# Bank35.net
KiCad netlist of a schematic drawn in Altium Designer
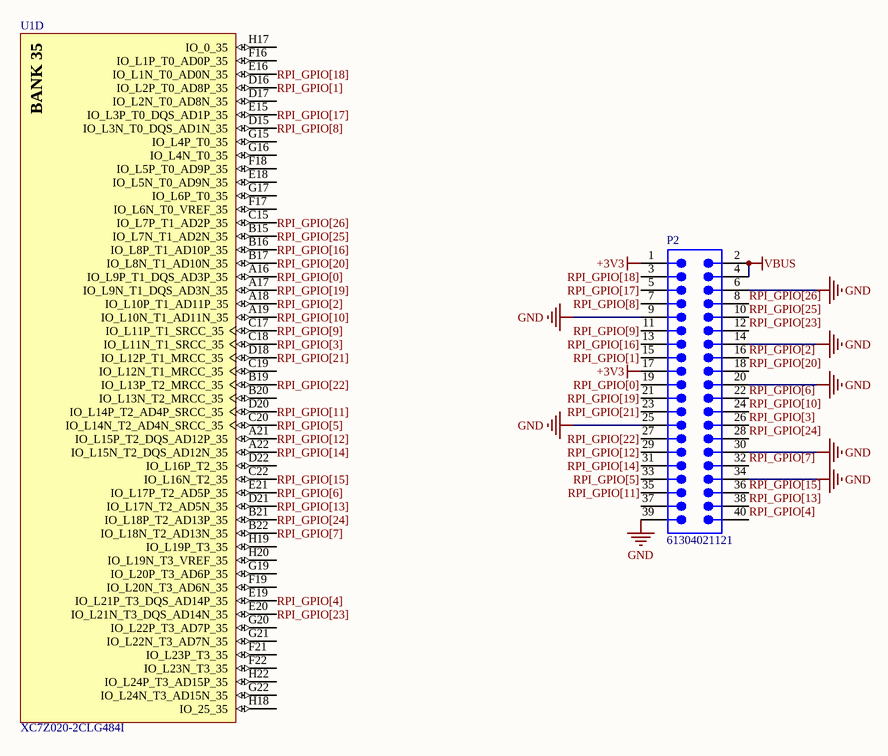
[diagram p0: Bank35.SchDoc]

(export (version "E")
  (design (tool "Eeschema 10.0.6"))
  (components
    (comp (ref "P2")
      (value "61304021121")
      (footprint "61304021121")
      (libsource (lib "Altium Content Vault") (part "Header_Male_2R_40P"))
    )
    (comp (ref "U1")
      (value "XC7Z020-2CLG484I")
      (footprint "CLG484")
      (fields (field (name "GENERIC PART NUMBER") "XC7Z020"))
      (libsource (lib "Altium Content Vault") (part "XNLX-XC7Z020-CLG484"))
    )
  )
  (nets
    (net (code "1") (name "+3V3") (class "Default")
      (node (ref "P2") (pin "1") (pinfunction "1_1") (pintype "passive"))
      (node (ref "P2") (pin "17") (pinfunction "17_17") (pintype "passive"))
    )
    (net (code "2") (name "/RPI_GPIO[0]") (class "Default")
      (node (ref "P2") (pin "19") (pinfunction "19_19") (pintype "passive"))
      (node (ref "U1") (pin "A16") (pinfunction "IO_L9P_T1_DQS_AD3P_35_A16") (pintype "bidirectional"))
    )
    (net (code "3") (name "/RPI_GPIO[1]") (class "Default")
      (node (ref "P2") (pin "15") (pinfunction "15_15") (pintype "passive"))
      (node (ref "U1") (pin "D16") (pinfunction "IO_L2P_T0_AD8P_35_D16") (pintype "bidirectional"))
    )
    (net (code "4") (name "/RPI_GPIO[2]") (class "Default")
      (node (ref "P2") (pin "16") (pinfunction "16_16") (pintype "passive"))
      (node (ref "U1") (pin "A18") (pinfunction "IO_L10P_T1_AD11P_35_A18") (pintype "bidirectional"))
    )
    (net (code "5") (name "/RPI_GPIO[3]") (class "Default")
      (node (ref "P2") (pin "26") (pinfunction "26_26") (pintype "passive"))
      (node (ref "U1") (pin "C18") (pinfunction "IO_L11N_T1_SRCC_35_C18") (pintype "bidirectional"))
    )
    (net (code "6") (name "/RPI_GPIO[4]") (class "Default")
      (node (ref "P2") (pin "40") (pinfunction "40_40") (pintype "passive"))
      (node (ref "U1") (pin "E19") (pinfunction "IO_L21P_T3_DQS_AD14P_35_E19") (pintype "bidirectional"))
    )
    (net (code "7") (name "/RPI_GPIO[5]") (class "Default")
      (node (ref "P2") (pin "33") (pinfunction "33_33") (pintype "passive"))
      (node (ref "U1") (pin "C20") (pinfunction "IO_L14N_T2_AD4N_SRCC_35_C20") (pintype "bidirectional"))
    )
    (net (code "8") (name "/RPI_GPIO[6]") (class "Default")
      (node (ref "P2") (pin "22") (pinfunction "22_22") (pintype "passive"))
      (node (ref "U1") (pin "E21") (pinfunction "IO_L17P_T2_AD5P_35_E21") (pintype "bidirectional"))
    )
    (net (code "9") (name "/RPI_GPIO[7]") (class "Default")
      (node (ref "P2") (pin "32") (pinfunction "32_32") (pintype "passive"))
      (node (ref "U1") (pin "B22") (pinfunction "IO_L18N_T2_AD13N_35_B22") (pintype "bidirectional"))
    )
    (net (code "10") (name "/RPI_GPIO[8]") (class "Default")
      (node (ref "P2") (pin "7") (pinfunction "7_7") (pintype "passive"))
      (node (ref "U1") (pin "D15") (pinfunction "IO_L3N_T0_DQS_AD1N_35_D15") (pintype "bidirectional"))
    )
    (net (code "11") (name "/RPI_GPIO[9]") (class "Default")
      (node (ref "P2") (pin "11") (pinfunction "11_11") (pintype "passive"))
      (node (ref "U1") (pin "C17") (pinfunction "IO_L11P_T1_SRCC_35_C17") (pintype "bidirectional"))
    )
    (net (code "12") (name "/RPI_GPIO[10]") (class "Default")
      (node (ref "P2") (pin "24") (pinfunction "24_24") (pintype "passive"))
      (node (ref "U1") (pin "A19") (pinfunction "IO_L10N_T1_AD11N_35_A19") (pintype "bidirectional"))
    )
    (net (code "13") (name "/RPI_GPIO[11]") (class "Default")
      (node (ref "P2") (pin "35") (pinfunction "35_35") (pintype "passive"))
      (node (ref "U1") (pin "D20") (pinfunction "IO_L14P_T2_AD4P_SRCC_35_D20") (pintype "bidirectional"))
    )
    (net (code "14") (name "/RPI_GPIO[12]") (class "Default")
      (node (ref "P2") (pin "29") (pinfunction "29_29") (pintype "passive"))
      (node (ref "U1") (pin "A21") (pinfunction "IO_L15P_T2_DQS_AD12P_35_A21") (pintype "bidirectional"))
    )
    (net (code "15") (name "/RPI_GPIO[13]") (class "Default")
      (node (ref "P2") (pin "38") (pinfunction "38_38") (pintype "passive"))
      (node (ref "U1") (pin "D21") (pinfunction "IO_L17N_T2_AD5N_35_D21") (pintype "bidirectional"))
    )
    (net (code "16") (name "/RPI_GPIO[14]") (class "Default")
      (node (ref "P2") (pin "31") (pinfunction "31_31") (pintype "passive"))
      (node (ref "U1") (pin "A22") (pinfunction "IO_L15N_T2_DQS_AD12N_35_A22") (pintype "bidirectional"))
    )
    (net (code "17") (name "/RPI_GPIO[15]") (class "Default")
      (node (ref "P2") (pin "36") (pinfunction "36_36") (pintype "passive"))
      (node (ref "U1") (pin "C22") (pinfunction "IO_L16N_T2_35_C22") (pintype "bidirectional"))
    )
    (net (code "18") (name "/RPI_GPIO[16]") (class "Default")
      (node (ref "P2") (pin "13") (pinfunction "13_13") (pintype "passive"))
      (node (ref "U1") (pin "B16") (pinfunction "IO_L8P_T1_AD10P_35_B16") (pintype "bidirectional"))
    )
    (net (code "19") (name "/RPI_GPIO[17]") (class "Default")
      (node (ref "P2") (pin "5") (pinfunction "5_5") (pintype "passive"))
      (node (ref "U1") (pin "E15") (pinfunction "IO_L3P_T0_DQS_AD1P_35_E15") (pintype "bidirectional"))
    )
    (net (code "20") (name "/RPI_GPIO[18]") (class "Default")
      (node (ref "P2") (pin "3") (pinfunction "3_3") (pintype "passive"))
      (node (ref "U1") (pin "E16") (pinfunction "IO_L1N_T0_AD0N_35_E16") (pintype "bidirectional"))
    )
    (net (code "21") (name "/RPI_GPIO[19]") (class "Default")
      (node (ref "P2") (pin "21") (pinfunction "21_21") (pintype "passive"))
      (node (ref "U1") (pin "A17") (pinfunction "IO_L9N_T1_DQS_AD3N_35_A17") (pintype "bidirectional"))
    )
    (net (code "22") (name "/RPI_GPIO[20]") (class "Default")
      (node (ref "P2") (pin "18") (pinfunction "18_18") (pintype "passive"))
      (node (ref "U1") (pin "B17") (pinfunction "IO_L8N_T1_AD10N_35_B17") (pintype "bidirectional"))
    )
    (net (code "23") (name "/RPI_GPIO[21]") (class "Default")
      (node (ref "P2") (pin "23") (pinfunction "23_23") (pintype "passive"))
      (node (ref "U1") (pin "D18") (pinfunction "IO_L12P_T1_MRCC_35_D18") (pintype "bidirectional"))
    )
    (net (code "24") (name "/RPI_GPIO[22]") (class "Default")
      (node (ref "P2") (pin "27") (pinfunction "27_27") (pintype "passive"))
      (node (ref "U1") (pin "B19") (pinfunction "IO_L13P_T2_MRCC_35_B19") (pintype "bidirectional"))
    )
    (net (code "25") (name "/RPI_GPIO[23]") (class "Default")
      (node (ref "P2") (pin "12") (pinfunction "12_12") (pintype "passive"))
      (node (ref "U1") (pin "E20") (pinfunction "IO_L21N_T3_DQS_AD14N_35_E20") (pintype "bidirectional"))
    )
    (net (code "26") (name "/RPI_GPIO[24]") (class "Default")
      (node (ref "P2") (pin "28") (pinfunction "28_28") (pintype "passive"))
      (node (ref "U1") (pin "B21") (pinfunction "IO_L18P_T2_AD13P_35_B21") (pintype "bidirectional"))
    )
    (net (code "27") (name "/RPI_GPIO[25]") (class "Default")
      (node (ref "P2") (pin "10") (pinfunction "10_10") (pintype "passive"))
      (node (ref "U1") (pin "B15") (pinfunction "IO_L7N_T1_AD2N_35_B15") (pintype "bidirectional"))
    )
    (net (code "28") (name "/RPI_GPIO[26]") (class "Default")
      (node (ref "P2") (pin "8") (pinfunction "8_8") (pintype "passive"))
      (node (ref "U1") (pin "C15") (pinfunction "IO_L7P_T1_AD2P_35_C15") (pintype "bidirectional"))
    )
    (net (code "29") (name "GND") (class "Default")
      (node (ref "P2") (pin "14") (pinfunction "14_14") (pintype "passive"))
      (node (ref "P2") (pin "20") (pinfunction "20_20") (pintype "passive"))
      (node (ref "P2") (pin "25") (pinfunction "25_25") (pintype "passive"))
      (node (ref "P2") (pin "30") (pinfunction "30_30") (pintype "passive"))
      (node (ref "P2") (pin "34") (pinfunction "34_34") (pintype "passive"))
      (node (ref "P2") (pin "39") (pinfunction "39_39") (pintype "passive"))
      (node (ref "P2") (pin "6") (pinfunction "6_6") (pintype "passive"))
      (node (ref "P2") (pin "9") (pinfunction "9_9") (pintype "passive"))
    )
    (net (code "30") (name "VBUS") (class "Default")
      (node (ref "P2") (pin "2") (pinfunction "2_2") (pintype "passive"))
      (node (ref "P2") (pin "4") (pinfunction "4_4") (pintype "passive"))
    )
    (net (code "31") (name "unconnected-(P2-Pad37)") (class "Default")
      (node (ref "P2") (pin "37") (pinfunction "37_37") (pintype "passive"))
    )
    (net (code "32") (name "unconnected-(U1D-IO_0_35-PadH17)") (class "Default")
      (node (ref "U1") (pin "H17") (pinfunction "IO_0_35_H17") (pintype "bidirectional"))
    )
    (net (code "33") (name "unconnected-(U1D-IO_25_35-PadH18)") (class "Default")
      (node (ref "U1") (pin "H18") (pinfunction "IO_25_35_H18") (pintype "bidirectional"))
    )
    (net (code "34") (name "unconnected-(U1D-IO_L1P_T0_AD0P_35-PadF16)") (class "Default")
      (node (ref "U1") (pin "F16") (pinfunction "IO_L1P_T0_AD0P_35_F16") (pintype "bidirectional"))
    )
    (net (code "35") (name "unconnected-(U1D-IO_L2N_T0_AD8N_35-PadD17)") (class "Default")
      (node (ref "U1") (pin "D17") (pinfunction "IO_L2N_T0_AD8N_35_D17") (pintype "bidirectional"))
    )
    (net (code "36") (name "unconnected-(U1D-IO_L4N_T0_35-PadG16)") (class "Default")
      (node (ref "U1") (pin "G16") (pinfunction "IO_L4N_T0_35_G16") (pintype "bidirectional"))
    )
    (net (code "37") (name "unconnected-(U1D-IO_L4P_T0_35-PadG15)") (class "Default")
      (node (ref "U1") (pin "G15") (pinfunction "IO_L4P_T0_35_G15") (pintype "bidirectional"))
    )
    (net (code "38") (name "unconnected-(U1D-IO_L5N_T0_AD9N_35-PadE18)") (class "Default")
      (node (ref "U1") (pin "E18") (pinfunction "IO_L5N_T0_AD9N_35_E18") (pintype "bidirectional"))
    )
    (net (code "39") (name "unconnected-(U1D-IO_L5P_T0_AD9P_35-PadF18)") (class "Default")
      (node (ref "U1") (pin "F18") (pinfunction "IO_L5P_T0_AD9P_35_F18") (pintype "bidirectional"))
    )
    (net (code "40") (name "unconnected-(U1D-IO_L6N_T0_VREF_35-PadF17)") (class "Default")
      (node (ref "U1") (pin "F17") (pinfunction "IO_L6N_T0_VREF_35_F17") (pintype "bidirectional"))
    )
    (net (code "41") (name "unconnected-(U1D-IO_L6P_T0_35-PadG17)") (class "Default")
      (node (ref "U1") (pin "G17") (pinfunction "IO_L6P_T0_35_G17") (pintype "bidirectional"))
    )
    (net (code "42") (name "unconnected-(U1D-IO_L12N_T1_MRCC_35-PadC19)") (class "Default")
      (node (ref "U1") (pin "C19") (pinfunction "IO_L12N_T1_MRCC_35_C19") (pintype "bidirectional"))
    )
    (net (code "43") (name "unconnected-(U1D-IO_L13N_T2_MRCC_35-PadB20)") (class "Default")
      (node (ref "U1") (pin "B20") (pinfunction "IO_L13N_T2_MRCC_35_B20") (pintype "bidirectional"))
    )
    (net (code "44") (name "unconnected-(U1D-IO_L16P_T2_35-PadD22)") (class "Default")
      (node (ref "U1") (pin "D22") (pinfunction "IO_L16P_T2_35_D22") (pintype "bidirectional"))
    )
    (net (code "45") (name "unconnected-(U1D-IO_L19N_T3_VREF_35-PadH20)") (class "Default")
      (node (ref "U1") (pin "H20") (pinfunction "IO_L19N_T3_VREF_35_H20") (pintype "bidirectional"))
    )
    (net (code "46") (name "unconnected-(U1D-IO_L19P_T3_35-PadH19)") (class "Default")
      (node (ref "U1") (pin "H19") (pinfunction "IO_L19P_T3_35_H19") (pintype "bidirectional"))
    )
    (net (code "47") (name "unconnected-(U1D-IO_L20N_T3_AD6N_35-PadF19)") (class "Default")
      (node (ref "U1") (pin "F19") (pinfunction "IO_L20N_T3_AD6N_35_F19") (pintype "bidirectional"))
    )
    (net (code "48") (name "unconnected-(U1D-IO_L20P_T3_AD6P_35-PadG19)") (class "Default")
      (node (ref "U1") (pin "G19") (pinfunction "IO_L20P_T3_AD6P_35_G19") (pintype "bidirectional"))
    )
    (net (code "49") (name "unconnected-(U1D-IO_L22N_T3_AD7N_35-PadG21)") (class "Default")
      (node (ref "U1") (pin "G21") (pinfunction "IO_L22N_T3_AD7N_35_G21") (pintype "bidirectional"))
    )
    (net (code "50") (name "unconnected-(U1D-IO_L22P_T3_AD7P_35-PadG20)") (class "Default")
      (node (ref "U1") (pin "G20") (pinfunction "IO_L22P_T3_AD7P_35_G20") (pintype "bidirectional"))
    )
    (net (code "51") (name "unconnected-(U1D-IO_L23N_T3_35-PadF22)") (class "Default")
      (node (ref "U1") (pin "F22") (pinfunction "IO_L23N_T3_35_F22") (pintype "bidirectional"))
    )
    (net (code "52") (name "unconnected-(U1D-IO_L23P_T3_35-PadF21)") (class "Default")
      (node (ref "U1") (pin "F21") (pinfunction "IO_L23P_T3_35_F21") (pintype "bidirectional"))
    )
    (net (code "53") (name "unconnected-(U1D-IO_L24N_T3_AD15N_35-PadG22)") (class "Default")
      (node (ref "U1") (pin "G22") (pinfunction "IO_L24N_T3_AD15N_35_G22") (pintype "bidirectional"))
    )
    (net (code "54") (name "unconnected-(U1D-IO_L24P_T3_AD15P_35-PadH22)") (class "Default")
      (node (ref "U1") (pin "H22") (pinfunction "IO_L24P_T3_AD15P_35_H22") (pintype "bidirectional"))
    )
  )
)
